# logger_Shield-v13.net
KiCad netlist of a schematic drawn in EAGLE
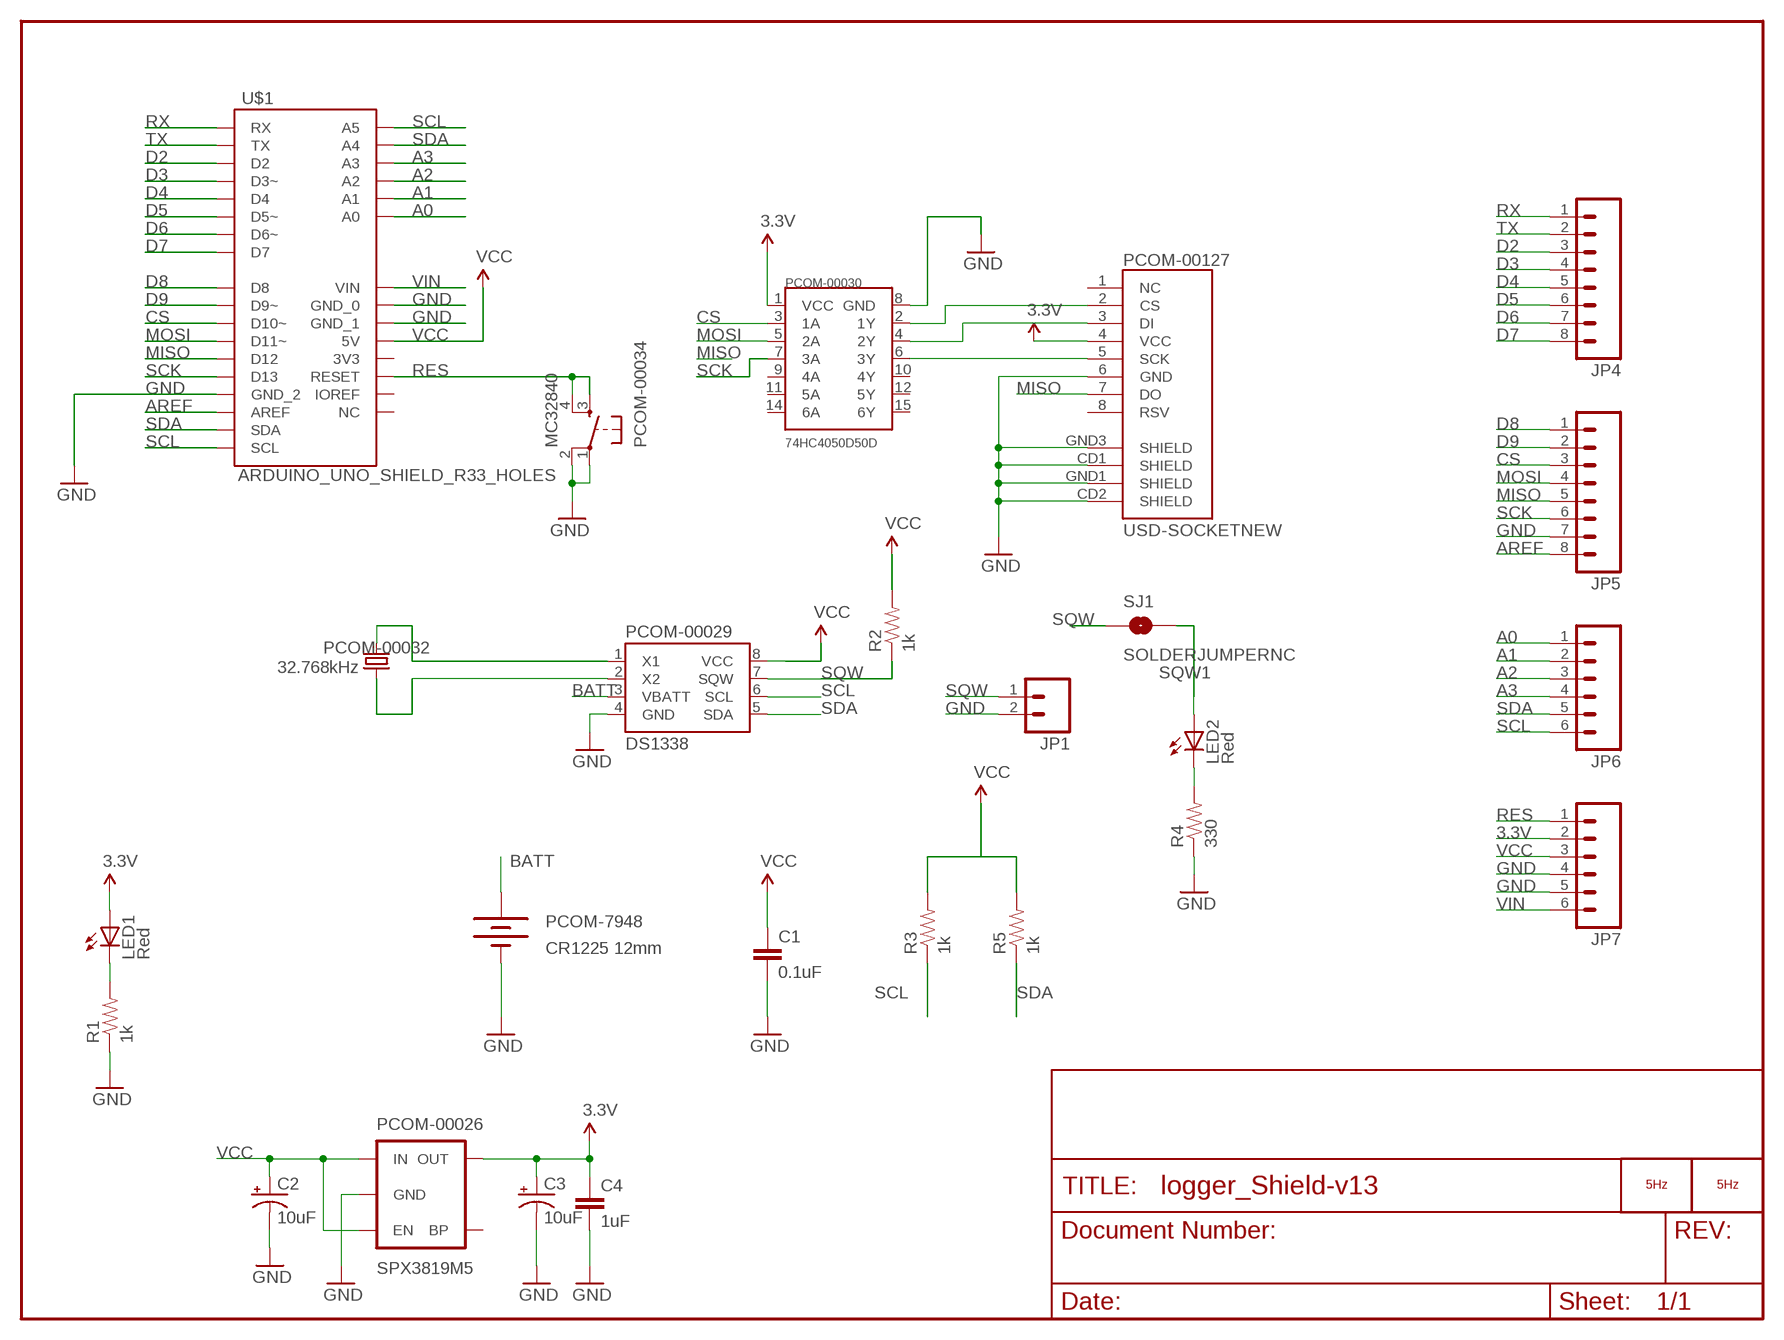
[diagram p0: schematic, sheet 1]

(export (version "E")
  (design (tool "Eeschema 10.0.6"))
  (components
    (comp (ref "C1")
      (value "0.1uF")
      (footprint "eagle-import:0603-CAP")
      (libsource (lib "eagle-import") (part "CAP0603-CAP"))
    )
    (comp (ref "C2")
      (value "10uF")
      (footprint "eagle-import:EIA3216")
      (libsource (lib "eagle-import") (part "CAP_POL1206"))
    )
    (comp (ref "C3")
      (value "10uF")
      (footprint "eagle-import:EIA3216")
      (libsource (lib "eagle-import") (part "CAP_POL1206"))
    )
    (comp (ref "C4")
      (value "1uF")
      (footprint "eagle-import:0603-CAP")
      (libsource (lib "eagle-import") (part "CAP0603-CAP"))
    )
    (comp (ref "JP1")
      (value "M02PTH")
      (footprint "eagle-import:1X02")
      (libsource (lib "eagle-import") (part "M02PTH"))
    )
    (comp (ref "JP4")
      (value "M08")
      (footprint "eagle-import:1X08")
      (libsource (lib "eagle-import") (part "M08"))
    )
    (comp (ref "JP5")
      (value "M08")
      (footprint "eagle-import:1X08")
      (libsource (lib "eagle-import") (part "M08"))
    )
    (comp (ref "JP6")
      (value "M06SIP")
      (footprint "eagle-import:1X06")
      (libsource (lib "eagle-import") (part "M06SIP"))
    )
    (comp (ref "JP7")
      (value "M06SIP")
      (footprint "eagle-import:1X06")
      (libsource (lib "eagle-import") (part "M06SIP"))
    )
    (comp (ref "LED1")
      (value "Red")
      (footprint "eagle-import:LED-0603")
      (libsource (lib "eagle-import") (part "LED0603"))
    )
    (comp (ref "LED2")
      (value "Red")
      (footprint "eagle-import:LED-0603")
      (libsource (lib "eagle-import") (part "LED0603"))
    )
    (comp (ref "LOGO1")
      (value "LOGO_5HZ_H_COOPER_15MM")
      (footprint "eagle-import:5HZ_LOGO_H_COOPER_15MM")
      (libsource (lib "eagle-import") (part "LOGO_5HZ_H_COOPER_15MM"))
    )
    (comp (ref "LOGO2")
      (value "LOGO_5HZ_MAIN_10MM")
      (footprint "eagle-import:5HZ_LOGO_MAIN_10MM")
      (libsource (lib "eagle-import") (part "LOGO_5HZ_MAIN_10MM"))
    )
    (comp (ref "PCOM-00026")
      (value "SPX3819M5")
      (footprint "eagle-import:SOT23-5")
      (libsource (lib "eagle-import") (part "V_REG_LDOSMD"))
    )
    (comp (ref "PCOM-00029")
      (value "DS1338")
      (footprint "eagle-import:SO08")
      (libsource (lib "eagle-import") (part "DS1307SO8"))
    )
    (comp (ref "PCOM-00030")
      (value "74HC4050D50D")
      (footprint "eagle-import:SO016")
      (libsource (lib "eagle-import") (part "HEX_CONVERTER"))
    )
    (comp (ref "PCOM-00032")
      (value "32.768kHz")
      (footprint "eagle-import:CRYSTAL-32KHZ-SMD")
      (libsource (lib "eagle-import") (part "CRYSTAL32-SMD"))
    )
    (comp (ref "PCOM-00034")
      (value "MC32840")
      (footprint "eagle-import:TACTILE_SWITCH_SMD")
      (libsource (lib "eagle-import") (part "TAC_SWITCHSMD"))
    )
    (comp (ref "PCOM-00127")
      (value "USD-SOCKETNEW")
      (footprint "eagle-import:MICRO-SD-SOCKET-PP")
      (libsource (lib "eagle-import") (part "USD-SOCKETNEW"))
    )
    (comp (ref "PCOM-7948")
      (value "CR1225 12mm")
      (footprint "eagle-import:BATTCON_12MM_PTH")
      (libsource (lib "eagle-import") (part "BATTERY12PTH"))
    )
    (comp (ref "R1")
      (value "1k")
      (footprint "eagle-import:0603-RES")
      (libsource (lib "eagle-import") (part "RESISTOR0603-RES"))
    )
    (comp (ref "R2")
      (value "1k")
      (footprint "eagle-import:0603-RES")
      (libsource (lib "eagle-import") (part "RESISTOR0603-RES"))
    )
    (comp (ref "R3")
      (value "1k")
      (footprint "eagle-import:0603-RES")
      (libsource (lib "eagle-import") (part "RESISTOR0603-RES"))
    )
    (comp (ref "R4")
      (value "330")
      (footprint "eagle-import:0603-RES")
      (libsource (lib "eagle-import") (part "RESISTOR0603-RES"))
    )
    (comp (ref "R5")
      (value "1k")
      (footprint "eagle-import:0603-RES")
      (libsource (lib "eagle-import") (part "RESISTOR0603-RES"))
    )
    (comp (ref "SJ1")
      (value "SOLDERJUMPERNC")
      (footprint "eagle-import:SJ_2S")
      (libsource (lib "eagle-import") (part "SOLDERJUMPERNC"))
    )
    (comp (ref "U$1")
      (value "ARDUINO_UNO_SHIELD_R33_HOLES")
      (footprint "eagle-import:UNO_R3_SHIELD_3_HOLES_NO_SILK")
      (libsource (lib "eagle-import") (part "ARDUINO_UNO_SHIELD_R33_HOLES"))
    )
  )
  (nets
    (net (code "1") (name "/A0") (class "Default")
      (node (ref "JP6") (pin "1") (pinfunction "1_1") (pintype "passive"))
      (node (ref "U$1") (pin "A0") (pinfunction "A0_A0") (pintype "bidirectional"))
    )
    (net (code "2") (name "/A1") (class "Default")
      (node (ref "JP6") (pin "2") (pinfunction "2_2") (pintype "passive"))
      (node (ref "U$1") (pin "A1") (pinfunction "A1_A1") (pintype "bidirectional"))
    )
    (net (code "3") (name "/A2") (class "Default")
      (node (ref "JP6") (pin "3") (pinfunction "3_3") (pintype "passive"))
      (node (ref "U$1") (pin "A2") (pinfunction "A2_A2") (pintype "bidirectional"))
    )
    (net (code "4") (name "/A3") (class "Default")
      (node (ref "JP6") (pin "4") (pinfunction "4_4") (pintype "passive"))
      (node (ref "U$1") (pin "A3") (pinfunction "A3_A3") (pintype "bidirectional"))
    )
    (net (code "5") (name "/AREF") (class "Default")
      (node (ref "JP5") (pin "8") (pinfunction "8_8") (pintype "passive"))
      (node (ref "U$1") (pin "AREF") (pinfunction "AREF_AREF") (pintype "bidirectional"))
    )
    (net (code "6") (name "/BATT") (class "Default")
      (node (ref "PCOM-00029") (pin "3") (pinfunction "VBATT_3") (pintype "bidirectional"))
      (node (ref "PCOM-7948") (pin "VCC@1") (pinfunction "+_VCC@1") (pintype "power_in"))
    )
    (net (code "7") (name "/CS") (class "Default")
      (node (ref "JP5") (pin "3") (pinfunction "3_3") (pintype "passive"))
      (node (ref "PCOM-00030") (pin "3") (pinfunction "1A_3") (pintype "bidirectional"))
      (node (ref "U$1") (pin "D10") (pinfunction "D10~{}_D10") (pintype "bidirectional"))
    )
    (net (code "8") (name "/D2") (class "Default")
      (node (ref "JP4") (pin "3") (pinfunction "3_3") (pintype "passive"))
      (node (ref "U$1") (pin "D2") (pinfunction "D2_D2") (pintype "bidirectional"))
    )
    (net (code "9") (name "/D3") (class "Default")
      (node (ref "JP4") (pin "4") (pinfunction "4_4") (pintype "passive"))
      (node (ref "U$1") (pin "D3") (pinfunction "D3~{}_D3") (pintype "bidirectional"))
    )
    (net (code "10") (name "/D4") (class "Default")
      (node (ref "JP4") (pin "5") (pinfunction "5_5") (pintype "passive"))
      (node (ref "U$1") (pin "D4") (pinfunction "D4_D4") (pintype "bidirectional"))
    )
    (net (code "11") (name "/D5") (class "Default")
      (node (ref "JP4") (pin "6") (pinfunction "6_6") (pintype "passive"))
      (node (ref "U$1") (pin "D5") (pinfunction "D5~{}_D5") (pintype "bidirectional"))
    )
    (net (code "12") (name "/D6") (class "Default")
      (node (ref "JP4") (pin "7") (pinfunction "7_7") (pintype "passive"))
      (node (ref "U$1") (pin "D6") (pinfunction "D6~{}_D6") (pintype "bidirectional"))
    )
    (net (code "13") (name "/D7") (class "Default")
      (node (ref "JP4") (pin "8") (pinfunction "8_8") (pintype "passive"))
      (node (ref "U$1") (pin "D7") (pinfunction "D7_D7") (pintype "bidirectional"))
    )
    (net (code "14") (name "/D8") (class "Default")
      (node (ref "JP5") (pin "1") (pinfunction "1_1") (pintype "passive"))
      (node (ref "U$1") (pin "D8") (pinfunction "D8_D8") (pintype "bidirectional"))
    )
    (net (code "15") (name "/D9") (class "Default")
      (node (ref "JP5") (pin "2") (pinfunction "2_2") (pintype "passive"))
      (node (ref "U$1") (pin "D9") (pinfunction "D9~{}_D9") (pintype "bidirectional"))
    )
    (net (code "16") (name "/MISO") (class "Default")
      (node (ref "JP5") (pin "5") (pinfunction "5_5") (pintype "passive"))
      (node (ref "PCOM-00127") (pin "7") (pinfunction "DO_7") (pintype "bidirectional"))
      (node (ref "U$1") (pin "D12") (pinfunction "D12_D12") (pintype "bidirectional"))
    )
    (net (code "17") (name "/MOSI") (class "Default")
      (node (ref "JP5") (pin "4") (pinfunction "4_4") (pintype "passive"))
      (node (ref "PCOM-00030") (pin "5") (pinfunction "2A_5") (pintype "bidirectional"))
      (node (ref "U$1") (pin "D11") (pinfunction "D11~{}_D11") (pintype "bidirectional"))
    )
    (net (code "18") (name "/RES") (class "Default")
      (node (ref "JP7") (pin "1") (pinfunction "1_1") (pintype "passive"))
      (node (ref "PCOM-00034") (pin "3") (pinfunction "3_3") (pintype "passive"))
      (node (ref "PCOM-00034") (pin "4") (pinfunction "4_4") (pintype "passive"))
      (node (ref "U$1") (pin "RES") (pinfunction "RESET_RES") (pintype "bidirectional"))
    )
    (net (code "19") (name "/RX") (class "Default")
      (node (ref "JP4") (pin "1") (pinfunction "1_1") (pintype "passive"))
      (node (ref "U$1") (pin "RX") (pinfunction "RX_RX") (pintype "bidirectional"))
    )
    (net (code "20") (name "/SCK") (class "Default")
      (node (ref "JP5") (pin "6") (pinfunction "6_6") (pintype "passive"))
      (node (ref "PCOM-00030") (pin "7") (pinfunction "3A_7") (pintype "bidirectional"))
      (node (ref "U$1") (pin "D13") (pinfunction "D13_D13") (pintype "bidirectional"))
    )
    (net (code "21") (name "/SCL") (class "Default")
      (node (ref "JP6") (pin "6") (pinfunction "6_6") (pintype "passive"))
      (node (ref "PCOM-00029") (pin "6") (pinfunction "SCL_6") (pintype "bidirectional"))
      (node (ref "R3") (pin "1") (pinfunction "1_1") (pintype "passive"))
      (node (ref "U$1") (pin "A5") (pinfunction "A5_A5") (pintype "bidirectional"))
      (node (ref "U$1") (pin "SCL") (pinfunction "SCL_SCL") (pintype "bidirectional"))
    )
    (net (code "22") (name "/SDA") (class "Default")
      (node (ref "JP6") (pin "5") (pinfunction "5_5") (pintype "passive"))
      (node (ref "PCOM-00029") (pin "5") (pinfunction "SDA_5") (pintype "bidirectional"))
      (node (ref "R5") (pin "1") (pinfunction "1_1") (pintype "passive"))
      (node (ref "U$1") (pin "A4") (pinfunction "A4_A4") (pintype "bidirectional"))
      (node (ref "U$1") (pin "SDA") (pinfunction "SDA_SDA") (pintype "bidirectional"))
    )
    (net (code "23") (name "/SQW") (class "Default")
      (node (ref "JP1") (pin "1") (pinfunction "1_1") (pintype "passive"))
      (node (ref "PCOM-00029") (pin "7") (pinfunction "SQW_7") (pintype "bidirectional"))
      (node (ref "R2") (pin "1") (pinfunction "1_1") (pintype "passive"))
      (node (ref "SJ1") (pin "1") (pinfunction "1_1") (pintype "passive"))
    )
    (net (code "24") (name "/SQW1") (class "Default")
      (node (ref "LED2") (pin "A") (pinfunction "A_A") (pintype "passive"))
      (node (ref "SJ1") (pin "2") (pinfunction "2_2") (pintype "passive"))
    )
    (net (code "25") (name "/TX") (class "Default")
      (node (ref "JP4") (pin "2") (pinfunction "2_2") (pintype "passive"))
      (node (ref "U$1") (pin "TX") (pinfunction "TX_TX") (pintype "bidirectional"))
    )
    (net (code "26") (name "/VIN") (class "Default")
      (node (ref "JP7") (pin "6") (pinfunction "6_6") (pintype "passive"))
      (node (ref "U$1") (pin "VIN") (pinfunction "VIN_VIN") (pintype "bidirectional"))
    )
    (net (code "27") (name "3.3V") (class "Default")
      (node (ref "C3") (pin "A") (pinfunction "+_A") (pintype "passive"))
      (node (ref "C4") (pin "1") (pinfunction "1_1") (pintype "passive"))
      (node (ref "JP7") (pin "2") (pinfunction "2_2") (pintype "passive"))
      (node (ref "LED1") (pin "A") (pinfunction "A_A") (pintype "passive"))
      (node (ref "PCOM-00026") (pin "5") (pinfunction "OUT_5") (pintype "passive"))
      (node (ref "PCOM-00030") (pin "1") (pinfunction "VCC_1") (pintype "bidirectional"))
      (node (ref "PCOM-00127") (pin "4") (pinfunction "VCC_4") (pintype "bidirectional"))
    )
    (net (code "28") (name "GND") (class "Default")
      (node (ref "C1") (pin "2") (pinfunction "2_2") (pintype "passive"))
      (node (ref "C2") (pin "C") (pinfunction "-_C") (pintype "passive"))
      (node (ref "C3") (pin "C") (pinfunction "-_C") (pintype "passive"))
      (node (ref "C4") (pin "2") (pinfunction "2_2") (pintype "passive"))
      (node (ref "JP1") (pin "2") (pinfunction "2_2") (pintype "passive"))
      (node (ref "JP5") (pin "7") (pinfunction "7_7") (pintype "passive"))
      (node (ref "JP7") (pin "4") (pinfunction "4_4") (pintype "passive"))
      (node (ref "JP7") (pin "5") (pinfunction "5_5") (pintype "passive"))
      (node (ref "PCOM-00026") (pin "2") (pinfunction "GND_2") (pintype "input"))
      (node (ref "PCOM-00029") (pin "4") (pinfunction "GND_4") (pintype "bidirectional"))
      (node (ref "PCOM-00030") (pin "8") (pinfunction "GND_8") (pintype "bidirectional"))
      (node (ref "PCOM-00034") (pin "1") (pinfunction "1_1") (pintype "passive"))
      (node (ref "PCOM-00034") (pin "2") (pinfunction "2_2") (pintype "passive"))
      (node (ref "PCOM-00127") (pin "6") (pinfunction "GND_6") (pintype "bidirectional"))
      (node (ref "PCOM-00127") (pin "CD1") (pinfunction "SHIELD_CD1") (pintype "bidirectional"))
      (node (ref "PCOM-00127") (pin "CD2") (pinfunction "SHIELD_CD2") (pintype "bidirectional"))
      (node (ref "PCOM-00127") (pin "GND1") (pinfunction "SHIELD_GND1") (pintype "bidirectional"))
      (node (ref "PCOM-00127") (pin "GND3") (pinfunction "SHIELD_GND3") (pintype "bidirectional"))
      (node (ref "PCOM-7948") (pin "GND") (pinfunction "-_GND") (pintype "power_in"))
      (node (ref "R1") (pin "1") (pinfunction "1_1") (pintype "passive"))
      (node (ref "R4") (pin "1") (pinfunction "1_1") (pintype "passive"))
      (node (ref "U$1") (pin "GND_0") (pinfunction "GND_0_GND_0") (pintype "bidirectional"))
      (node (ref "U$1") (pin "GND_1") (pinfunction "GND_1_GND_1") (pintype "bidirectional"))
      (node (ref "U$1") (pin "GND_2") (pinfunction "GND_2_GND_2") (pintype "bidirectional"))
    )
    (net (code "29") (name "Net-(LED1-PadC)") (class "Default")
      (node (ref "LED1") (pin "C") (pinfunction "C_C") (pintype "passive"))
      (node (ref "R1") (pin "2") (pinfunction "2_2") (pintype "passive"))
    )
    (net (code "30") (name "Net-(LED2-PadC)") (class "Default")
      (node (ref "LED2") (pin "C") (pinfunction "C_C") (pintype "passive"))
      (node (ref "R4") (pin "2") (pinfunction "2_2") (pintype "passive"))
    )
    (net (code "31") (name "Net-(PCOM-00029-X1)") (class "Default")
      (node (ref "PCOM-00029") (pin "1") (pinfunction "X1_1") (pintype "bidirectional"))
      (node (ref "PCOM-00032") (pin "X2") (pinfunction "2_X2") (pintype "passive"))
    )
    (net (code "32") (name "Net-(PCOM-00029-X2)") (class "Default")
      (node (ref "PCOM-00029") (pin "2") (pinfunction "X2_2") (pintype "bidirectional"))
      (node (ref "PCOM-00032") (pin "X1") (pinfunction "1_X1") (pintype "passive"))
    )
    (net (code "33") (name "Net-(PCOM-00030-1Y)") (class "Default")
      (node (ref "PCOM-00030") (pin "2") (pinfunction "1Y_2") (pintype "bidirectional"))
      (node (ref "PCOM-00127") (pin "2") (pinfunction "CS_2") (pintype "bidirectional"))
    )
    (net (code "34") (name "Net-(PCOM-00030-2Y)") (class "Default")
      (node (ref "PCOM-00030") (pin "4") (pinfunction "2Y_4") (pintype "bidirectional"))
      (node (ref "PCOM-00127") (pin "3") (pinfunction "DI_3") (pintype "bidirectional"))
    )
    (net (code "35") (name "Net-(PCOM-00030-3Y)") (class "Default")
      (node (ref "PCOM-00030") (pin "6") (pinfunction "3Y_6") (pintype "bidirectional"))
      (node (ref "PCOM-00127") (pin "5") (pinfunction "SCK_5") (pintype "bidirectional"))
    )
    (net (code "36") (name "VCC") (class "Default")
      (node (ref "C1") (pin "1") (pinfunction "1_1") (pintype "passive"))
      (node (ref "C2") (pin "A") (pinfunction "+_A") (pintype "passive"))
      (node (ref "JP7") (pin "3") (pinfunction "3_3") (pintype "passive"))
      (node (ref "PCOM-00026") (pin "1") (pinfunction "IN_1") (pintype "input"))
      (node (ref "PCOM-00026") (pin "3") (pinfunction "EN_3") (pintype "input"))
      (node (ref "PCOM-00029") (pin "8") (pinfunction "VCC_8") (pintype "bidirectional"))
      (node (ref "R2") (pin "2") (pinfunction "2_2") (pintype "passive"))
      (node (ref "R3") (pin "2") (pinfunction "2_2") (pintype "passive"))
      (node (ref "R5") (pin "2") (pinfunction "2_2") (pintype "passive"))
      (node (ref "U$1") (pin "5V") (pinfunction "5V_5V") (pintype "bidirectional"))
    )
    (net (code "37") (name "unconnected-(PCOM-00026-BP-Pad4)") (class "Default")
      (node (ref "PCOM-00026") (pin "4") (pinfunction "BP_4") (pintype "input"))
    )
    (net (code "38") (name "unconnected-(PCOM-00030-4A-Pad9)") (class "Default")
      (node (ref "PCOM-00030") (pin "9") (pinfunction "4A_9") (pintype "bidirectional"))
    )
    (net (code "39") (name "unconnected-(PCOM-00030-4Y-Pad10)") (class "Default")
      (node (ref "PCOM-00030") (pin "10") (pinfunction "4Y_10") (pintype "bidirectional"))
    )
    (net (code "40") (name "unconnected-(PCOM-00030-5A-Pad11)") (class "Default")
      (node (ref "PCOM-00030") (pin "11") (pinfunction "5A_11") (pintype "bidirectional"))
    )
    (net (code "41") (name "unconnected-(PCOM-00030-5Y-Pad12)") (class "Default")
      (node (ref "PCOM-00030") (pin "12") (pinfunction "5Y_12") (pintype "bidirectional"))
    )
    (net (code "42") (name "unconnected-(PCOM-00030-6A-Pad14)") (class "Default")
      (node (ref "PCOM-00030") (pin "14") (pinfunction "6A_14") (pintype "bidirectional"))
    )
    (net (code "43") (name "unconnected-(PCOM-00030-6Y-Pad15)") (class "Default")
      (node (ref "PCOM-00030") (pin "15") (pinfunction "6Y_15") (pintype "bidirectional"))
    )
    (net (code "44") (name "unconnected-(PCOM-00127-NC-Pad1)") (class "Default")
      (node (ref "PCOM-00127") (pin "1") (pinfunction "NC_1") (pintype "bidirectional"))
    )
    (net (code "45") (name "unconnected-(PCOM-00127-RSV-Pad8)") (class "Default")
      (node (ref "PCOM-00127") (pin "8") (pinfunction "RSV_8") (pintype "bidirectional"))
    )
    (net (code "46") (name "unconnected-(U$1-3V3-Pad3.3V)") (class "Default")
      (node (ref "U$1") (pin "3.3V") (pinfunction "3V3_3.3V") (pintype "bidirectional"))
    )
    (net (code "47") (name "unconnected-(U$1-PadIOREF)") (class "Default")
      (node (ref "U$1") (pin "IOREF") (pinfunction "IOREF_IOREF") (pintype "bidirectional"))
    )
    (net (code "48") (name "unconnected-(U$1-PadNC)") (class "Default")
      (node (ref "U$1") (pin "NC") (pinfunction "NC_NC") (pintype "no_connect"))
    )
  )
)
